# STM32_MCU.net
KiCad netlist of a schematic drawn in Altium Designer
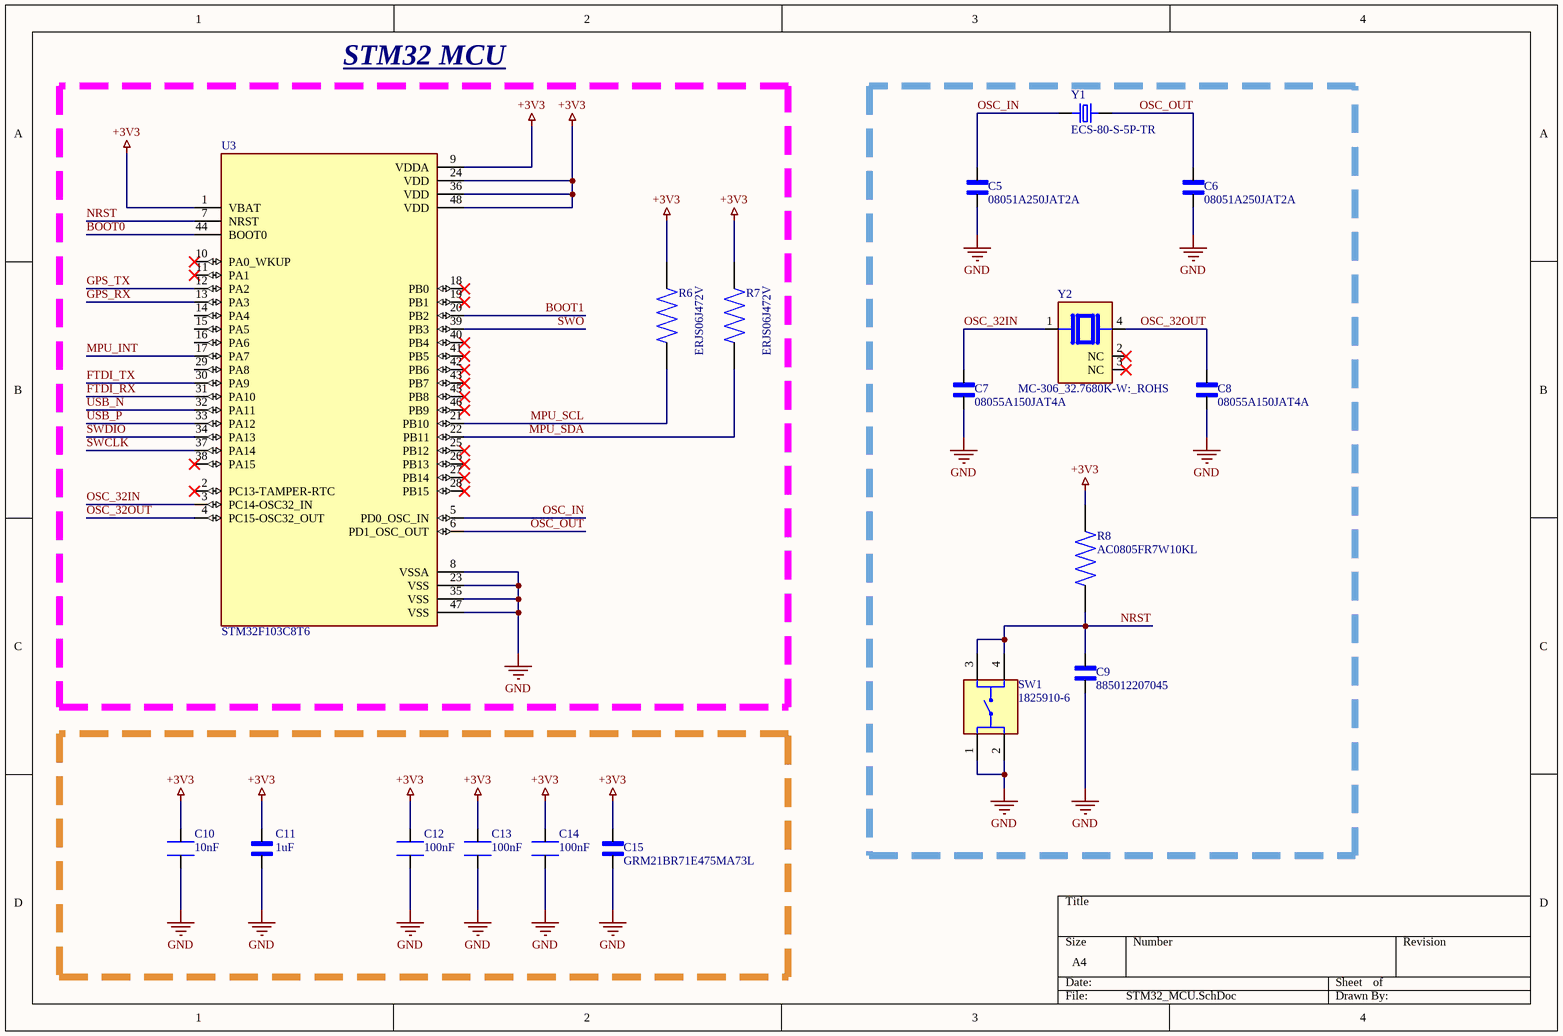
[diagram p0: STM32_MCU.SchDoc]

(export (version "E")
  (design (tool "Eeschema 10.0.6"))
  (components
    (comp (ref "C5")
      (value "08051A250JAT2A")
      (footprint "08051A250JAT2A:CAPC2012X94N")
      (fields (field (name "MF") "{'manufacturer': u'AVX'}"))
      (libsource (lib "*") (part "08051A250JAT2A"))
    )
    (comp (ref "C6")
      (value "08051A250JAT2A")
      (footprint "08051A250JAT2A:CAPC2012X94N")
      (fields (field (name "MF") "{'manufacturer': u'AVX'}"))
      (libsource (lib "*") (part "08051A250JAT2A"))
    )
    (comp (ref "C7")
      (value "08055A150JAT4A")
      (footprint "08055A150JAT4A:CAPC2012X140N")
      (description "Cap Ceramic 15pF 50V C0G 5% SMD 0805 125Â°C Paper T/R")
      (fields (field (name "MF") "{'manufacturer': u'AVX'}"))
      (libsource (lib "*") (part "08055A150JAT4A"))
    )
    (comp (ref "C8")
      (value "08055A150JAT4A")
      (footprint "08055A150JAT4A:CAPC2012X140N")
      (description "Cap Ceramic 15pF 50V C0G 5% SMD 0805 125Â°C Paper T/R")
      (fields (field (name "MF") "{'manufacturer': u'AVX'}"))
      (libsource (lib "*") (part "08055A150JAT4A"))
    )
    (comp (ref "C9")
      (value "885012207045")
      (footprint "885012207045:WCAP-CSGP_885012207045")
      (fields (field (name "MF") "{'manufacturer': u'Wurth Electronics Inc'}"))
      (libsource (lib "*") (part "885012207045"))
    )
    (comp (ref "C10")
      (value "10nF")
      (footprint "885382207009:WCAP-CSST_885382207009")
      (fields
        (field (name "MF") "{'manufacturer': u'Wurth Electronics Inc'}")
        (field (name "MP") "885382207009")
      )
      (libsource (lib "*") (part "885382207009"))
    )
    (comp (ref "C11")
      (value "1uF")
      (footprint "GRM21BR71H105KA12L:CAPC2012X135N")
      (description "Cap Ceramic 1uF 50V X7R 10% SMD 0805 125Ã‚Â°C Embossed T/R")
      (fields (field (name "MF") "{'manufacturer': u'Murata'}") (field (name "MP") "GRM21BR71H105KA12L"))
      (libsource (lib "*") (part "GRM21BR71H105KA12L"))
    )
    (comp (ref "C12")
      (value "100nF")
      (footprint "885382207007:WCAP-CSST_885382207007")
      (fields
        (field (name "MF") "{'manufacturer': u'Wurth Electronics Inc'}")
        (field (name "MP") "885382207007")
      )
      (libsource (lib "*") (part "885382207007"))
    )
    (comp (ref "C13")
      (value "100nF")
      (footprint "885382207007:WCAP-CSST_885382207007")
      (fields
        (field (name "MF") "{'manufacturer': u'Wurth Electronics Inc'}")
        (field (name "MP") "885382207007")
      )
      (libsource (lib "*") (part "885382207007"))
    )
    (comp (ref "C14")
      (value "100nF")
      (footprint "885382207007:WCAP-CSST_885382207007")
      (fields
        (field (name "MF") "{'manufacturer': u'Wurth Electronics Inc'}")
        (field (name "MP") "885382207007")
      )
      (libsource (lib "*") (part "885382207007"))
    )
    (comp (ref "C15")
      (value "GRM21BR71E475MA73L")
      (footprint "GRM21BR71E475MA73L:CAPC2012X135N")
      (description "CAP CER 4.7UF 25V X7R 0805")
      (fields (field (name "MF") "{'manufacturer': u'Murata'}"))
      (libsource (lib "*") (part "GRM21BR71E475MA73L"))
    )
    (comp (ref "R6")
      (value "ERJS06J472V")
      (footprint "ERJ-S06J472V:RES_ERJS06J472V")
      (fields (field (name "MF") "{'manufacturer': u'Panasonic'}"))
      (libsource (lib "*") (part "ERJS06J472V"))
    )
    (comp (ref "R7")
      (value "ERJS06J472V")
      (footprint "ERJ-S06J472V:RES_ERJS06J472V")
      (fields (field (name "MF") "{'manufacturer': u'Panasonic'}"))
      (libsource (lib "*") (part "ERJS06J472V"))
    )
    (comp (ref "R8")
      (value "AC0805FR7W10KL")
      (footprint "AC0805FR7W10KL:RESC2012X60N")
      (description "RES SMD 18 OHM 5% 1/8W 0805")
      (fields (field (name "MF") "{'manufacturer': u'Yageo Corporation'}"))
      (libsource (lib "*") (part "AC0805FR7W10KL"))
    )
    (comp (ref "SW1")
      (value "1825910-6")
      (footprint "1825910-6:SW_1825910-6-4")
      (description "Switch Tactile OFF (ON) SPST Round Button PC Pins 0.05A 24VDC 100000Cycles 1.57N Thru-Hole Loose")
      (fields (field (name "MF") "{'manufacturer': u'TE Connectivity'}"))
      (libsource (lib "1825910-6") (part "1825910-6"))
    )
    (comp (ref "U3")
      (value "STM32F103C8T6")
      (footprint "STM32F103C8T6:QFP50P900X900X160-48N")
      (fields (field (name "MF") "{'manufacturer': u'STMicroelectronics'}"))
      (libsource (lib "*") (part "STM32F103C8T6"))
    )
    (comp (ref "Y1")
      (value "ECS-80-S-5P-TR")
      (footprint "ECS-80-S-5P-TR:XTAL_ECS-80-S-5P-TR")
      (description "CRYSTAL SMD")
      (fields (field (name "MF") "{'manufacturer': u'ECS International'}"))
      (libsource (lib "*") (part "ECS-80-S-5P-TR"))
    )
    (comp (ref "Y2")
      (value "MC-306_32.7680K-W:_ROHS")
      (footprint "MC-306 32.7680K-W_ ROHS:XTAL_MC-306_32.7680K-W:_ROHS")
      (fields (field (name "MF") "{'manufacturer': u'EPSON'}") (field (name "MP") "MC-306 32.7680K-W: ROHS"))
      (libsource (lib "*") (part "MC-306_32.7680K-W{colon}_ROHS"))
    )
  )
  (nets
    (net (code "1") (name "+3V3") (class "Default")
      (node (ref "C10") (pin "2") (pinfunction "2_2") (pintype "passive"))
      (node (ref "C11") (pin "1") (pinfunction "1_1") (pintype "passive"))
      (node (ref "C12") (pin "2") (pinfunction "2_2") (pintype "passive"))
      (node (ref "C13") (pin "2") (pinfunction "2_2") (pintype "passive"))
      (node (ref "C14") (pin "2") (pinfunction "2_2") (pintype "passive"))
      (node (ref "C15") (pin "1") (pinfunction "1_1") (pintype "passive"))
      (node (ref "R6") (pin "2") (pinfunction "2_2") (pintype "passive"))
      (node (ref "R7") (pin "2") (pinfunction "2_2") (pintype "passive"))
      (node (ref "R8") (pin "2") (pinfunction "2_2") (pintype "passive"))
      (node (ref "U3") (pin "1") (pinfunction "VBAT_1") (pintype "power_in"))
      (node (ref "U3") (pin "24") (pinfunction "VDD_24") (pintype "power_in"))
      (node (ref "U3") (pin "36") (pinfunction "VDD_36") (pintype "power_in"))
      (node (ref "U3") (pin "48") (pinfunction "VDD_48") (pintype "power_in"))
      (node (ref "U3") (pin "9") (pinfunction "VDDA_9") (pintype "power_in"))
    )
    (net (code "2") (name "/BOOT0") (class "Default")
      (node (ref "U3") (pin "44") (pinfunction "BOOT0_44") (pintype "passive"))
    )
    (net (code "3") (name "/BOOT1") (class "Default")
      (node (ref "U3") (pin "20") (pinfunction "PB2_20") (pintype "bidirectional"))
    )
    (net (code "4") (name "/FTDI_RX") (class "Default")
      (node (ref "U3") (pin "31") (pinfunction "PA10_31") (pintype "bidirectional"))
    )
    (net (code "5") (name "/FTDI_TX") (class "Default")
      (node (ref "U3") (pin "30") (pinfunction "PA9_30") (pintype "bidirectional"))
    )
    (net (code "6") (name "/GPS_RX") (class "Default")
      (node (ref "U3") (pin "13") (pinfunction "PA3_13") (pintype "bidirectional"))
    )
    (net (code "7") (name "/GPS_TX") (class "Default")
      (node (ref "U3") (pin "12") (pinfunction "PA2_12") (pintype "bidirectional"))
    )
    (net (code "8") (name "/MPU_INT") (class "Default")
      (node (ref "U3") (pin "17") (pinfunction "PA7_17") (pintype "bidirectional"))
    )
    (net (code "9") (name "/MPU_SCL") (class "Default")
      (node (ref "R6") (pin "1") (pinfunction "1_1") (pintype "passive"))
      (node (ref "U3") (pin "21") (pinfunction "PB10_21") (pintype "bidirectional"))
    )
    (net (code "10") (name "/MPU_SDA") (class "Default")
      (node (ref "R7") (pin "1") (pinfunction "1_1") (pintype "passive"))
      (node (ref "U3") (pin "22") (pinfunction "PB11_22") (pintype "bidirectional"))
    )
    (net (code "11") (name "/NRST") (class "Default")
      (node (ref "C9") (pin "2") (pinfunction "2_2") (pintype "passive"))
      (node (ref "R8") (pin "1") (pinfunction "1_1") (pintype "passive"))
      (node (ref "SW1") (pin "3") (pinfunction "3_3") (pintype "passive"))
      (node (ref "SW1") (pin "4") (pinfunction "4_4") (pintype "passive"))
      (node (ref "U3") (pin "7") (pinfunction "NRST_7") (pintype "passive"))
    )
    (net (code "12") (name "/OSC_32IN") (class "Default")
      (node (ref "C7") (pin "1") (pinfunction "1_1") (pintype "passive"))
      (node (ref "U3") (pin "3") (pinfunction "PC14-OSC32_IN_3") (pintype "bidirectional"))
      (node (ref "Y2") (pin "1") (pinfunction "1_1") (pintype "passive"))
    )
    (net (code "13") (name "/OSC_32OUT") (class "Default")
      (node (ref "C8") (pin "1") (pinfunction "1_1") (pintype "passive"))
      (node (ref "U3") (pin "4") (pinfunction "PC15-OSC32_OUT_4") (pintype "bidirectional"))
      (node (ref "Y2") (pin "4") (pinfunction "2_4") (pintype "passive"))
    )
    (net (code "14") (name "/OSC_IN") (class "Default")
      (node (ref "C5") (pin "2") (pinfunction "2_2") (pintype "passive"))
      (node (ref "U3") (pin "5") (pinfunction "PD0_OSC_IN_5") (pintype "bidirectional"))
      (node (ref "Y1") (pin "1") (pinfunction "1_1") (pintype "passive"))
    )
    (net (code "15") (name "/OSC_OUT") (class "Default")
      (node (ref "C6") (pin "2") (pinfunction "2_2") (pintype "passive"))
      (node (ref "U3") (pin "6") (pinfunction "PD1_OSC_OUT_6") (pintype "bidirectional"))
      (node (ref "Y1") (pin "2") (pinfunction "2_2") (pintype "passive"))
    )
    (net (code "16") (name "/SWCLK") (class "Default")
      (node (ref "U3") (pin "37") (pinfunction "PA14_37") (pintype "bidirectional"))
    )
    (net (code "17") (name "/SWDIO") (class "Default")
      (node (ref "U3") (pin "34") (pinfunction "PA13_34") (pintype "bidirectional"))
    )
    (net (code "18") (name "/SWO") (class "Default")
      (node (ref "U3") (pin "39") (pinfunction "PB3_39") (pintype "bidirectional"))
    )
    (net (code "19") (name "/USB_N") (class "Default")
      (node (ref "U3") (pin "32") (pinfunction "PA11_32") (pintype "bidirectional"))
    )
    (net (code "20") (name "/USB_P") (class "Default")
      (node (ref "U3") (pin "33") (pinfunction "PA12_33") (pintype "bidirectional"))
    )
    (net (code "21") (name "GND") (class "Default")
      (node (ref "C10") (pin "1") (pinfunction "1_1") (pintype "passive"))
      (node (ref "C11") (pin "2") (pinfunction "2_2") (pintype "passive"))
      (node (ref "C12") (pin "1") (pinfunction "1_1") (pintype "passive"))
      (node (ref "C13") (pin "1") (pinfunction "1_1") (pintype "passive"))
      (node (ref "C14") (pin "1") (pinfunction "1_1") (pintype "passive"))
      (node (ref "C15") (pin "2") (pinfunction "2_2") (pintype "passive"))
      (node (ref "C5") (pin "1") (pinfunction "1_1") (pintype "passive"))
      (node (ref "C6") (pin "1") (pinfunction "1_1") (pintype "passive"))
      (node (ref "C7") (pin "2") (pinfunction "2_2") (pintype "passive"))
      (node (ref "C8") (pin "2") (pinfunction "2_2") (pintype "passive"))
      (node (ref "C9") (pin "1") (pinfunction "1_1") (pintype "passive"))
      (node (ref "SW1") (pin "1") (pinfunction "1_1") (pintype "passive"))
      (node (ref "SW1") (pin "2") (pinfunction "2_2") (pintype "passive"))
      (node (ref "U3") (pin "23") (pinfunction "VSS_23") (pintype "power_in"))
      (node (ref "U3") (pin "35") (pinfunction "VSS_35") (pintype "power_in"))
      (node (ref "U3") (pin "47") (pinfunction "VSS_47") (pintype "power_in"))
      (node (ref "U3") (pin "8") (pinfunction "VSSA_8") (pintype "power_in"))
    )
    (net (code "22") (name "unconnected-(U3-PA0_WKUP-Pad10)") (class "Default")
      (node (ref "U3") (pin "10") (pinfunction "PA0_WKUP_10") (pintype "bidirectional+no_connect"))
    )
    (net (code "23") (name "unconnected-(U3-PA1-Pad11)") (class "Default")
      (node (ref "U3") (pin "11") (pinfunction "PA1_11") (pintype "bidirectional+no_connect"))
    )
    (net (code "24") (name "unconnected-(U3-PA4-Pad14)") (class "Default")
      (node (ref "U3") (pin "14") (pinfunction "PA4_14") (pintype "bidirectional"))
    )
    (net (code "25") (name "unconnected-(U3-PA5-Pad15)") (class "Default")
      (node (ref "U3") (pin "15") (pinfunction "PA5_15") (pintype "bidirectional"))
    )
    (net (code "26") (name "unconnected-(U3-PA6-Pad16)") (class "Default")
      (node (ref "U3") (pin "16") (pinfunction "PA6_16") (pintype "bidirectional"))
    )
    (net (code "27") (name "unconnected-(U3-PA8-Pad29)") (class "Default")
      (node (ref "U3") (pin "29") (pinfunction "PA8_29") (pintype "bidirectional"))
    )
    (net (code "28") (name "unconnected-(U3-PA15-Pad38)") (class "Default")
      (node (ref "U3") (pin "38") (pinfunction "PA15_38") (pintype "bidirectional+no_connect"))
    )
    (net (code "29") (name "unconnected-(U3-PB0-Pad18)") (class "Default")
      (node (ref "U3") (pin "18") (pinfunction "PB0_18") (pintype "bidirectional+no_connect"))
    )
    (net (code "30") (name "unconnected-(U3-PB1-Pad19)") (class "Default")
      (node (ref "U3") (pin "19") (pinfunction "PB1_19") (pintype "bidirectional+no_connect"))
    )
    (net (code "31") (name "unconnected-(U3-PB4-Pad40)") (class "Default")
      (node (ref "U3") (pin "40") (pinfunction "PB4_40") (pintype "bidirectional+no_connect"))
    )
    (net (code "32") (name "unconnected-(U3-PB5-Pad41)") (class "Default")
      (node (ref "U3") (pin "41") (pinfunction "PB5_41") (pintype "bidirectional+no_connect"))
    )
    (net (code "33") (name "unconnected-(U3-PB6-Pad42)") (class "Default")
      (node (ref "U3") (pin "42") (pinfunction "PB6_42") (pintype "bidirectional+no_connect"))
    )
    (net (code "34") (name "unconnected-(U3-PB7-Pad43)") (class "Default")
      (node (ref "U3") (pin "43") (pinfunction "PB7_43") (pintype "bidirectional+no_connect"))
    )
    (net (code "35") (name "unconnected-(U3-PB8-Pad45)") (class "Default")
      (node (ref "U3") (pin "45") (pinfunction "PB8_45") (pintype "bidirectional+no_connect"))
    )
    (net (code "36") (name "unconnected-(U3-PB9-Pad46)") (class "Default")
      (node (ref "U3") (pin "46") (pinfunction "PB9_46") (pintype "bidirectional+no_connect"))
    )
    (net (code "37") (name "unconnected-(U3-PB12-Pad25)") (class "Default")
      (node (ref "U3") (pin "25") (pinfunction "PB12_25") (pintype "bidirectional+no_connect"))
    )
    (net (code "38") (name "unconnected-(U3-PB13-Pad26)") (class "Default")
      (node (ref "U3") (pin "26") (pinfunction "PB13_26") (pintype "bidirectional+no_connect"))
    )
    (net (code "39") (name "unconnected-(U3-PB14-Pad27)") (class "Default")
      (node (ref "U3") (pin "27") (pinfunction "PB14_27") (pintype "bidirectional+no_connect"))
    )
    (net (code "40") (name "unconnected-(U3-PB15-Pad28)") (class "Default")
      (node (ref "U3") (pin "28") (pinfunction "PB15_28") (pintype "bidirectional+no_connect"))
    )
    (net (code "41") (name "unconnected-(U3-PC13-TAMPER-RTC-Pad2)") (class "Default")
      (node (ref "U3") (pin "2") (pinfunction "PC13-TAMPER-RTC_2") (pintype "bidirectional+no_connect"))
    )
    (net (code "42") (name "unconnected-(Y2-NC-Pad2)") (class "Default")
      (node (ref "Y2") (pin "2") (pinfunction "NC_2") (pintype "passive+no_connect"))
    )
    (net (code "43") (name "unconnected-(Y2-NC-Pad3)") (class "Default")
      (node (ref "Y2") (pin "3") (pinfunction "NC_3") (pintype "passive+no_connect"))
    )
  )
)
